# Power.net
KiCad netlist of a schematic drawn in Altium Designer
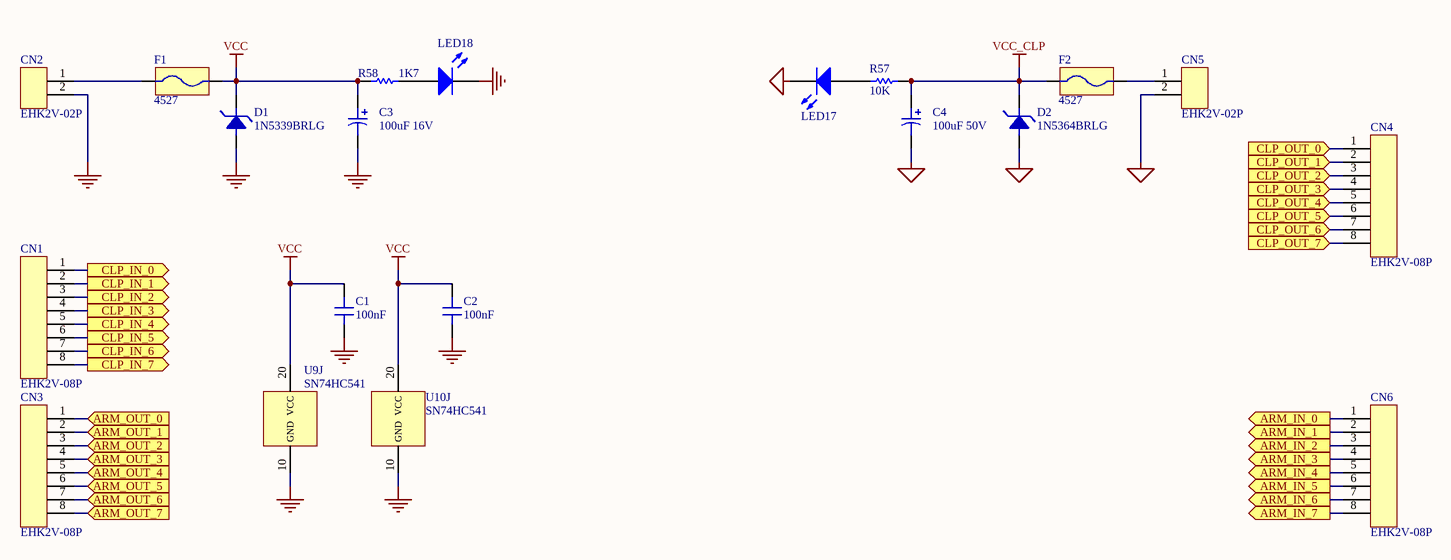
[diagram p0: Power.SchDoc]

(export (version "E")
  (design (tool "Eeschema 10.0.6"))
  (components
    (comp (ref "C1")
      (value "100nF")
      (footprint "DiskCapacitor")
      (description "Capacitor")
      (libsource (lib "Basic") (part "Capacitor"))
    )
    (comp (ref "C2")
      (value "100nF")
      (footprint "DiskCapacitor")
      (description "Capacitor")
      (libsource (lib "Basic") (part "Capacitor"))
    )
    (comp (ref "C3")
      (value "100uF 16V")
      (footprint "ECA 5x11")
      (libsource (lib "Panasonic") (part "ECA1CM101"))
    )
    (comp (ref "C4")
      (value "100uF 50V")
      (footprint "ECA 8x11.5")
      (libsource (lib "Panasonic") (part "ECA1HM101"))
    )
    (comp (ref "CN1")
      (value "EHK2V-08P")
      (footprint "EHK2V-08P")
      (description "PCB Terminal Blocks")
      (libsource (lib "") (part "EHK2V-08P_1"))
    )
    (comp (ref "CN2")
      (value "EHK2V-02P")
      (footprint "EHK2V-02P")
      (description "PCB Terminal Blocks")
      (libsource (lib "") (part "EHK2V-02P_1"))
    )
    (comp (ref "CN3")
      (value "EHK2V-08P")
      (footprint "EHK2V-08P")
      (description "PCB Terminal Blocks")
      (libsource (lib "") (part "EHK2V-08P_1"))
    )
    (comp (ref "CN4")
      (value "EHK2V-08P")
      (footprint "EHK2V-08P")
      (description "PCB Terminal Blocks")
      (libsource (lib "Dinkle") (part "EHK2V-08P"))
    )
    (comp (ref "CN5")
      (value "EHK2V-02P")
      (footprint "EHK2V-02P")
      (description "PCB Terminal Blocks")
      (libsource (lib "Dinkle") (part "EHK2V-02P"))
    )
    (comp (ref "CN6")
      (value "EHK2V-08P")
      (footprint "EHK2V-08P")
      (description "PCB Terminal Blocks")
      (libsource (lib "Dinkle") (part "EHK2V-08P"))
    )
    (comp (ref "D1")
      (value "1N5339BRLG")
      (footprint "DO-15")
      (description "5V6 @ 5W")
      (libsource (lib "Basic") (part "Diode Zener"))
    )
    (comp (ref "D2")
      (value "1N5364BRLG")
      (footprint "DO-15")
      (description "33V @ 5W")
      (libsource (lib "Basic") (part "Diode Zener"))
    )
    (comp (ref "F1")
      (value "4527")
      (footprint "4527")
      (description "5mm PC FUSE HOLDER")
      (libsource (lib "Keystone") (part "4527"))
    )
    (comp (ref "F2")
      (value "4527")
      (footprint "4527")
      (description "5mm PC FUSE HOLDER")
      (libsource (lib "Keystone") (part "4527"))
    )
    (comp (ref "LED17")
      (value "151053YS04500")
      (footprint "Type 5mm")
      (description "THT LED round mono-color waterclear, WL-TMRW, Yellow")
      (fields (field (name "MANUFACTURER") "Wuerth Elektronik"))
      (libsource (lib "Altium Content Vault") (part "WE-LED_K1A2-2"))
    )
    (comp (ref "LED18")
      (value "151053YS04500")
      (footprint "Type 5mm")
      (description "THT LED round mono-color waterclear, WL-TMRW, Yellow")
      (fields (field (name "MANUFACTURER") "Wuerth Elektronik"))
      (libsource (lib "Altium Content Vault") (part "WE-LED_K1A2-2"))
    )
    (comp (ref "R57")
      (value "10K")
      (footprint "AXIAL-0.3")
      (description "Resistor")
      (fields (field (name "Comment") "Res1") (field (name "PUBLISHER") "Altium Limited"))
      (libsource (lib "Miscellaneous Devices") (part "Res1"))
    )
    (comp (ref "R58")
      (value "1K7")
      (footprint "AXIAL-0.3")
      (description "Resistor")
      (fields (field (name "Comment") "Res1") (field (name "PUBLISHER") "Altium Limited"))
      (libsource (lib "Miscellaneous Devices") (part "Res1"))
    )
    (comp (ref "U9")
      (value "SN74HC541")
      (footprint "PDIP20")
      (description "Octal Buffers and Line Drivers With 3-State Outputs")
      (libsource (lib "Texas Instruments") (part "SN74HC541"))
    )
    (comp (ref "U10")
      (value "SN74HC541")
      (footprint "PDIP20")
      (description "Octal Buffers and Line Drivers With 3-State Outputs")
      (libsource (lib "Texas Instruments") (part "SN74HC541"))
    )
  )
  (nets
    (net (code "1") (name "/ARM_IN_0") (class "Default")
      (node (ref "CN6") (pin "1") (pinfunction "1_1") (pintype "passive"))
    )
    (net (code "2") (name "/ARM_IN_1") (class "Default")
      (node (ref "CN6") (pin "2") (pinfunction "2_2") (pintype "passive"))
    )
    (net (code "3") (name "/ARM_IN_2") (class "Default")
      (node (ref "CN6") (pin "3") (pinfunction "3_3") (pintype "passive"))
    )
    (net (code "4") (name "/ARM_IN_3") (class "Default")
      (node (ref "CN6") (pin "4") (pinfunction "4_4") (pintype "passive"))
    )
    (net (code "5") (name "/ARM_IN_4") (class "Default")
      (node (ref "CN6") (pin "5") (pinfunction "5_5") (pintype "passive"))
    )
    (net (code "6") (name "/ARM_IN_5") (class "Default")
      (node (ref "CN6") (pin "6") (pinfunction "6_6") (pintype "passive"))
    )
    (net (code "7") (name "/ARM_IN_6") (class "Default")
      (node (ref "CN6") (pin "7") (pinfunction "7_7") (pintype "passive"))
    )
    (net (code "8") (name "/ARM_IN_7") (class "Default")
      (node (ref "CN6") (pin "8") (pinfunction "8_8") (pintype "passive"))
    )
    (net (code "9") (name "/ARM_OUT_0") (class "Default")
      (node (ref "CN3") (pin "1") (pinfunction "1_1") (pintype "passive"))
    )
    (net (code "10") (name "/ARM_OUT_1") (class "Default")
      (node (ref "CN3") (pin "2") (pinfunction "2_2") (pintype "passive"))
    )
    (net (code "11") (name "/ARM_OUT_2") (class "Default")
      (node (ref "CN3") (pin "3") (pinfunction "3_3") (pintype "passive"))
    )
    (net (code "12") (name "/ARM_OUT_3") (class "Default")
      (node (ref "CN3") (pin "4") (pinfunction "4_4") (pintype "passive"))
    )
    (net (code "13") (name "/ARM_OUT_4") (class "Default")
      (node (ref "CN3") (pin "5") (pinfunction "5_5") (pintype "passive"))
    )
    (net (code "14") (name "/ARM_OUT_5") (class "Default")
      (node (ref "CN3") (pin "6") (pinfunction "6_6") (pintype "passive"))
    )
    (net (code "15") (name "/ARM_OUT_6") (class "Default")
      (node (ref "CN3") (pin "7") (pinfunction "7_7") (pintype "passive"))
    )
    (net (code "16") (name "/ARM_OUT_7") (class "Default")
      (node (ref "CN3") (pin "8") (pinfunction "8_8") (pintype "passive"))
    )
    (net (code "17") (name "/CLP_IN_0") (class "Default")
      (node (ref "CN1") (pin "1") (pinfunction "1_1") (pintype "passive"))
    )
    (net (code "18") (name "/CLP_IN_1") (class "Default")
      (node (ref "CN1") (pin "2") (pinfunction "2_2") (pintype "passive"))
    )
    (net (code "19") (name "/CLP_IN_2") (class "Default")
      (node (ref "CN1") (pin "3") (pinfunction "3_3") (pintype "passive"))
    )
    (net (code "20") (name "/CLP_IN_3") (class "Default")
      (node (ref "CN1") (pin "4") (pinfunction "4_4") (pintype "passive"))
    )
    (net (code "21") (name "/CLP_IN_4") (class "Default")
      (node (ref "CN1") (pin "5") (pinfunction "5_5") (pintype "passive"))
    )
    (net (code "22") (name "/CLP_IN_5") (class "Default")
      (node (ref "CN1") (pin "6") (pinfunction "6_6") (pintype "passive"))
    )
    (net (code "23") (name "/CLP_IN_6") (class "Default")
      (node (ref "CN1") (pin "7") (pinfunction "7_7") (pintype "passive"))
    )
    (net (code "24") (name "/CLP_IN_7") (class "Default")
      (node (ref "CN1") (pin "8") (pinfunction "8_8") (pintype "passive"))
    )
    (net (code "25") (name "/CLP_OUT_0") (class "Default")
      (node (ref "CN4") (pin "1") (pinfunction "1_1") (pintype "passive"))
    )
    (net (code "26") (name "/CLP_OUT_1") (class "Default")
      (node (ref "CN4") (pin "2") (pinfunction "2_2") (pintype "passive"))
    )
    (net (code "27") (name "/CLP_OUT_2") (class "Default")
      (node (ref "CN4") (pin "3") (pinfunction "3_3") (pintype "passive"))
    )
    (net (code "28") (name "/CLP_OUT_3") (class "Default")
      (node (ref "CN4") (pin "4") (pinfunction "4_4") (pintype "passive"))
    )
    (net (code "29") (name "/CLP_OUT_4") (class "Default")
      (node (ref "CN4") (pin "5") (pinfunction "5_5") (pintype "passive"))
    )
    (net (code "30") (name "/CLP_OUT_5") (class "Default")
      (node (ref "CN4") (pin "6") (pinfunction "6_6") (pintype "passive"))
    )
    (net (code "31") (name "/CLP_OUT_6") (class "Default")
      (node (ref "CN4") (pin "7") (pinfunction "7_7") (pintype "passive"))
    )
    (net (code "32") (name "/CLP_OUT_7") (class "Default")
      (node (ref "CN4") (pin "8") (pinfunction "8_8") (pintype "passive"))
    )
    (net (code "33") (name "CLP_GND") (class "Default")
      (node (ref "C4") (pin "2") (pinfunction "2_2") (pintype "passive"))
      (node (ref "CN5") (pin "2") (pinfunction "2_2") (pintype "passive"))
      (node (ref "D2") (pin "2") (pinfunction "2_2") (pintype "passive"))
      (node (ref "LED17") (pin "1") (pinfunction "K_1") (pintype "passive"))
    )
    (net (code "34") (name "GND") (class "Default")
      (node (ref "C1") (pin "1") (pinfunction "1_1") (pintype "passive"))
      (node (ref "C2") (pin "1") (pinfunction "1_1") (pintype "passive"))
      (node (ref "C3") (pin "2") (pinfunction "2_2") (pintype "passive"))
      (node (ref "CN2") (pin "2") (pinfunction "2_2") (pintype "passive"))
      (node (ref "D1") (pin "2") (pinfunction "2_2") (pintype "passive"))
      (node (ref "LED18") (pin "1") (pinfunction "K_1") (pintype "passive"))
      (node (ref "U10") (pin "10") (pinfunction "GND_10") (pintype "power_in"))
      (node (ref "U9") (pin "10") (pinfunction "GND_10") (pintype "power_in"))
    )
    (net (code "35") (name "Net-(CN2-Pad1)") (class "Default")
      (node (ref "CN2") (pin "1") (pinfunction "1_1") (pintype "passive"))
      (node (ref "F1") (pin "1") (pinfunction "1_1") (pintype "passive"))
    )
    (net (code "36") (name "Net-(CN5-Pad1)") (class "Default")
      (node (ref "CN5") (pin "1") (pinfunction "1_1") (pintype "passive"))
      (node (ref "F2") (pin "2") (pinfunction "2_2") (pintype "passive"))
    )
    (net (code "37") (name "Net-(LED17-A)") (class "Default")
      (node (ref "LED17") (pin "2") (pinfunction "A_2") (pintype "passive"))
      (node (ref "R57") (pin "1") (pinfunction "1_1") (pintype "passive"))
    )
    (net (code "38") (name "Net-(LED18-A)") (class "Default")
      (node (ref "LED18") (pin "2") (pinfunction "A_2") (pintype "passive"))
      (node (ref "R58") (pin "1") (pinfunction "1_1") (pintype "passive"))
    )
    (net (code "39") (name "VCC") (class "Default")
      (node (ref "C1") (pin "2") (pinfunction "2_2") (pintype "passive"))
      (node (ref "C2") (pin "2") (pinfunction "2_2") (pintype "passive"))
      (node (ref "C3") (pin "1") (pinfunction "1_1") (pintype "passive"))
      (node (ref "D1") (pin "1") (pinfunction "1_1") (pintype "passive"))
      (node (ref "F1") (pin "2") (pinfunction "2_2") (pintype "passive"))
      (node (ref "R58") (pin "2") (pinfunction "2_2") (pintype "passive"))
      (node (ref "U10") (pin "20") (pinfunction "VCC_20") (pintype "power_in"))
      (node (ref "U9") (pin "20") (pinfunction "VCC_20") (pintype "power_in"))
    )
    (net (code "40") (name "VCC_CLP") (class "Default")
      (node (ref "C4") (pin "1") (pinfunction "1_1") (pintype "passive"))
      (node (ref "D2") (pin "1") (pinfunction "1_1") (pintype "passive"))
      (node (ref "F2") (pin "1") (pinfunction "1_1") (pintype "passive"))
      (node (ref "R57") (pin "2") (pinfunction "2_2") (pintype "passive"))
    )
  )
)
